# 1_Shutdown.net
KiCad netlist of a schematic drawn in Altium Designer
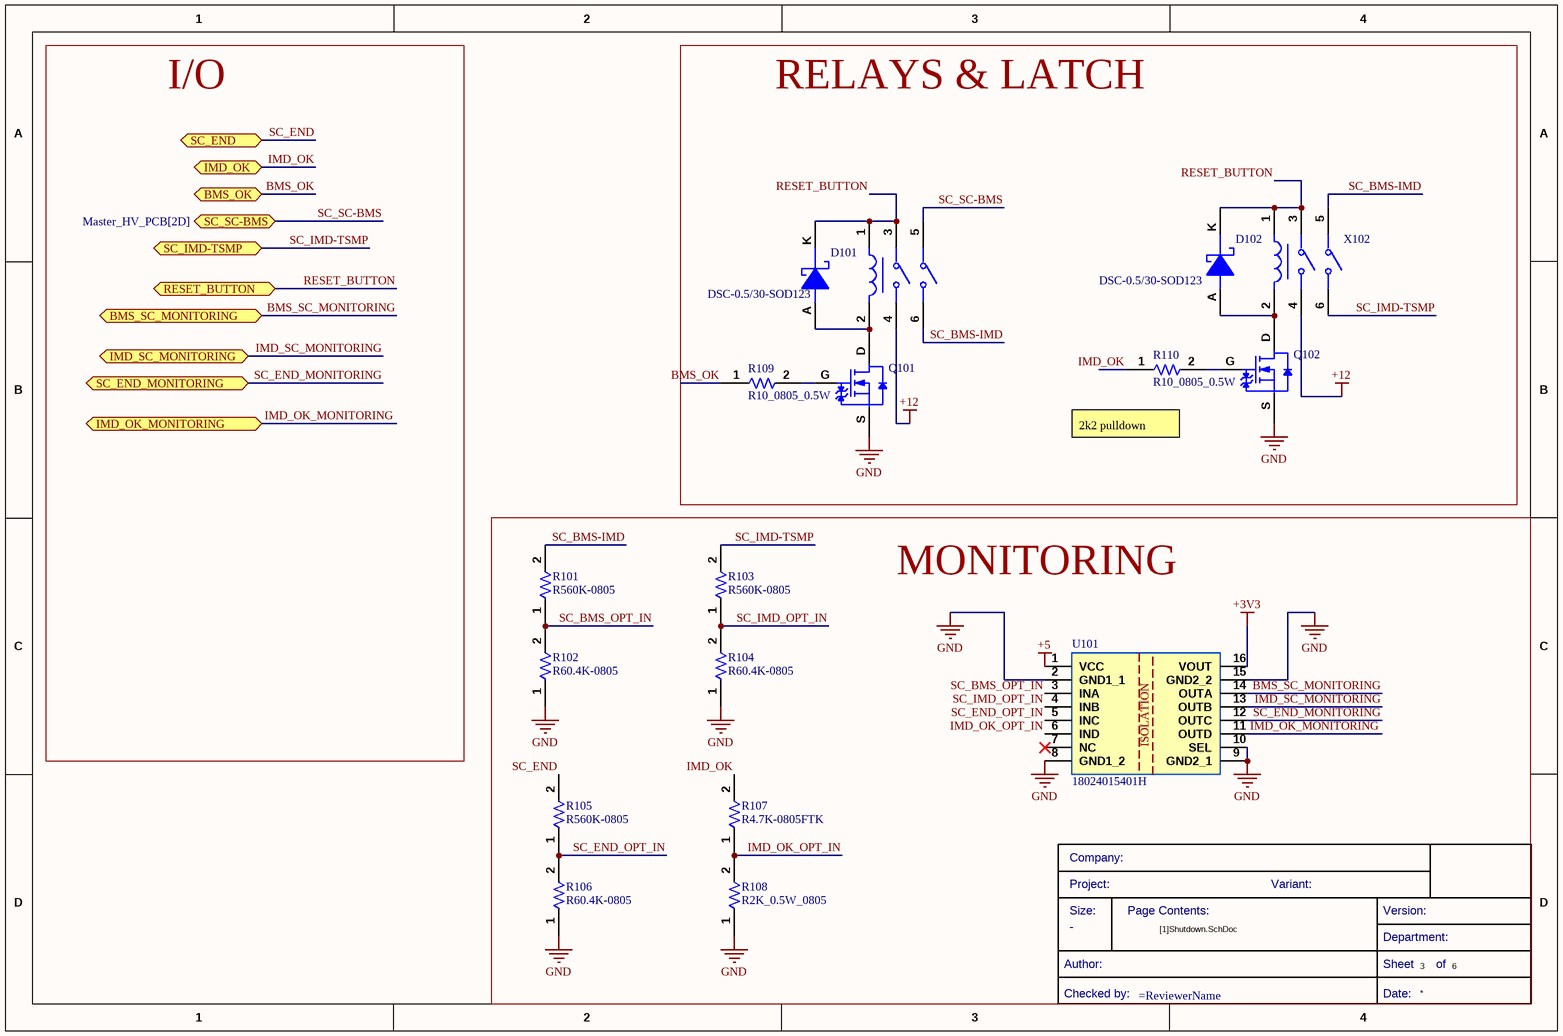
[diagram p0: [1]Shutdown.SchDoc]

(export (version "E")
  (design (tool "Eeschema 10.0.6"))
  (components
    (comp (ref "D101")
      (value "DSC-0.5/30-SOD123")
      (footprint "DSC-SOD123")
      (description "VR=30V IF=500mA 30pF P=410mW")
      (fields (field (name ".CREATOR") "GP"))
      (libsource (lib "EMEA- E-Tech Racing- I'Escola d'Enginyeria de Barcelona Est") (part "DSC-0.5/30-SOD123"))
    )
    (comp (ref "D102")
      (value "DSC-0.5/30-SOD123")
      (footprint "DSC-SOD123")
      (description "VR=30V IF=500mA 30pF P=410mW")
      (fields (field (name ".CREATOR") "GP"))
      (libsource (lib "EMEA- E-Tech Racing- I'Escola d'Enginyeria de Barcelona Est") (part "DSC-0.5/30-SOD123"))
    )
    (comp (ref "Q101")
      (value "SQ2318CES-T1_GE3")
      (footprint "SOT95P245X110-3N")
      (description "Mosfet, N-channel, 40V, 7A, SOT-23 Rohs Compliant: Yes")
      (libsource (lib "EMEA- E-Tech Racing- I'Escola d'Enginyeria de Barcelona Est") (part "TRT-NCH-3/35-CPH"))
    )
    (comp (ref "Q102")
      (value "SQ2318CES-T1_GE3")
      (footprint "SOT95P245X110-3N")
      (description "Mosfet, N-channel, 40V, 7A, SOT-23 Rohs Compliant: Yes")
      (libsource (lib "EMEA- E-Tech Racing- I'Escola d'Enginyeria de Barcelona Est") (part "TRT-NCH-3/35-CPH"))
    )
    (comp (ref "R101")
      (value "R560K-0805")
      (footprint "0805")
      (fields (field (name "POWER") "125mW") (field (name "TOLERANCE") "1%"))
      (libsource (lib "EMEA- E-Tech Racing- I'Escola d'Enginyeria de Barcelona Est") (part "R9.09K-1206FTK"))
    )
    (comp (ref "R102")
      (value "R60.4K-0805")
      (footprint "FP-CR0805-IPC_A")
      (fields (field (name "TOLERANCE") "1%") (field (name "POWER") "125mW"))
      (libsource (lib "EMEA- E-Tech Racing- I'Escola d'Enginyeria de Barcelona Est") (part "R9.09K-1206FTK"))
    )
    (comp (ref "R103")
      (value "R560K-0805")
      (footprint "0805")
      (fields (field (name "POWER") "125mW") (field (name "TOLERANCE") "1%"))
      (libsource (lib "EMEA- E-Tech Racing- I'Escola d'Enginyeria de Barcelona Est") (part "R9.09K-1206FTK"))
    )
    (comp (ref "R104")
      (value "R60.4K-0805")
      (footprint "FP-CR0805-IPC_A")
      (fields (field (name "TOLERANCE") "1%") (field (name "POWER") "125mW"))
      (libsource (lib "EMEA- E-Tech Racing- I'Escola d'Enginyeria de Barcelona Est") (part "R9.09K-1206FTK"))
    )
    (comp (ref "R105")
      (value "R560K-0805")
      (footprint "0805")
      (fields (field (name "POWER") "125mW") (field (name "TOLERANCE") "1%"))
      (libsource (lib "EMEA- E-Tech Racing- I'Escola d'Enginyeria de Barcelona Est") (part "R9.09K-1206FTK"))
    )
    (comp (ref "R106")
      (value "R60.4K-0805")
      (footprint "FP-CR0805-IPC_A")
      (fields (field (name "TOLERANCE") "1%") (field (name "POWER") "125mW"))
      (libsource (lib "EMEA- E-Tech Racing- I'Escola d'Enginyeria de Barcelona Est") (part "R9.09K-1206FTK"))
    )
    (comp (ref "R107")
      (value "R4.7K-0805FTK")
      (footprint "R0805FTK")
      (description "Res Thick Film 0805 4.7K Ohm 5% 1/8W ±200ppm/°C Molded SMD SMD Paper Tape on Plastic Reel")
      (fields (field (name "TOLERANCE") "5%") (field (name ".CREATOR") "DR"))
      (libsource (lib "EMEA- E-Tech Racing- I'Escola d'Enginyeria de Barcelona Est") (part "R9.09K-1206FTK"))
    )
    (comp (ref "R108")
      (value "R2K_0.5W_0805")
      (footprint "0805")
      (fields
        (field (name "POWER") "500mW")
        (field (name "TOLERANCE") "1%")
        (field (name "PART NUMBER") "CRCW08052K00FKEAHP")
      )
      (libsource (lib "EMEA- E-Tech Racing- I'Escola d'Enginyeria de Barcelona Est") (part "R9.09K-1206FTK"))
    )
    (comp (ref "R109")
      (value "R10_0805_0.5W")
      (footprint "0805")
      (fields (field (name "TOLERANCE") "1%") (field (name "POWER") "500mW"))
      (libsource (lib "EMEA- E-Tech Racing- I'Escola d'Enginyeria de Barcelona Est") (part "R9.09K-1206FTK"))
    )
    (comp (ref "R110")
      (value "R10_0805_0.5W")
      (footprint "0805")
      (fields (field (name "TOLERANCE") "1%") (field (name "POWER") "500mW"))
      (libsource (lib "EMEA- E-Tech Racing- I'Escola d'Enginyeria de Barcelona Est") (part "R9.09K-1206FTK"))
    )
    (comp (ref "U101")
      (value "18024015401H")
      (footprint "18024015401H")
      (description "Digital Isolator, 4CH, 125DEG C, WSOIC16 Rohs Compliant: Yes")
      (libsource (lib "EMEA- E-Tech Racing- I'Escola d'Enginyeria de Barcelona Est") (part "18024015401H"))
    )
    (comp (ref "X101")
      (value "RTE44012F")
      (footprint "RTE44012F-Footprint-1")
      (libsource (lib "EMEA- E-Tech Racing- I'Escola d'Enginyeria de Barcelona Est") (part "Relay_G81C"))
    )
    (comp (ref "X102")
      (value "RTE44012F")
      (footprint "RTE44012F-Footprint-1")
      (libsource (lib "EMEA- E-Tech Racing- I'Escola d'Enginyeria de Barcelona Est") (part "Relay_G81C"))
    )
  )
  (nets
    (net (code "1") (name "+3V3") (class "Default")
      (node (ref "U101") (pin "16") (pinfunction "VOUT_16") (pintype "passive"))
    )
    (net (code "2") (name "+5") (class "Default")
      (node (ref "U101") (pin "1") (pinfunction "VCC_1") (pintype "passive"))
    )
    (net (code "3") (name "+12") (class "Default")
      (node (ref "X101") (pin "4") (pinfunction "4_4") (pintype "passive"))
      (node (ref "X102") (pin "4") (pinfunction "4_4") (pintype "passive"))
    )
    (net (code "4") (name "/BMS_OK") (class "Default")
      (node (ref "R109") (pin "1") (pinfunction "1_1") (pintype "passive"))
    )
    (net (code "5") (name "/BMS_SC_MONITORING") (class "Default")
      (node (ref "U101") (pin "14") (pinfunction "OUTA_14") (pintype "passive"))
    )
    (net (code "6") (name "/IMD_OK") (class "Default")
      (node (ref "R107") (pin "2") (pinfunction "2_2") (pintype "passive"))
      (node (ref "R110") (pin "1") (pinfunction "1_1") (pintype "passive"))
    )
    (net (code "7") (name "/IMD_OK_MONITORING") (class "Default")
      (node (ref "U101") (pin "11") (pinfunction "OUTD_11") (pintype "passive"))
    )
    (net (code "8") (name "/IMD_OK_OPT_IN") (class "Default")
      (node (ref "R107") (pin "1") (pinfunction "1_1") (pintype "passive"))
      (node (ref "R108") (pin "2") (pinfunction "2_2") (pintype "passive"))
      (node (ref "U101") (pin "6") (pinfunction "IND_6") (pintype "passive"))
    )
    (net (code "9") (name "/IMD_SC_MONITORING") (class "Default")
      (node (ref "U101") (pin "13") (pinfunction "OUTB_13") (pintype "passive"))
    )
    (net (code "10") (name "/RESET_BUTTON") (class "Default")
      (node (ref "D101") (pin "K") (pinfunction "K_K") (pintype "passive"))
      (node (ref "D102") (pin "K") (pinfunction "K_K") (pintype "passive"))
      (node (ref "X101") (pin "1") (pinfunction "1_1") (pintype "passive"))
      (node (ref "X101") (pin "3") (pinfunction "3_3") (pintype "passive"))
      (node (ref "X102") (pin "1") (pinfunction "1_1") (pintype "passive"))
      (node (ref "X102") (pin "3") (pinfunction "3_3") (pintype "passive"))
    )
    (net (code "11") (name "/SC_BMS-IMD") (class "Default")
      (node (ref "R101") (pin "2") (pinfunction "2_2") (pintype "passive"))
      (node (ref "X101") (pin "6") (pinfunction "6_6") (pintype "passive"))
      (node (ref "X102") (pin "5") (pinfunction "5_5") (pintype "passive"))
    )
    (net (code "12") (name "/SC_BMS_OPT_IN") (class "Default")
      (node (ref "R101") (pin "1") (pinfunction "1_1") (pintype "passive"))
      (node (ref "R102") (pin "2") (pinfunction "2_2") (pintype "passive"))
      (node (ref "U101") (pin "3") (pinfunction "INA_3") (pintype "passive"))
    )
    (net (code "13") (name "/SC_END") (class "Default")
      (node (ref "R105") (pin "2") (pinfunction "2_2") (pintype "passive"))
    )
    (net (code "14") (name "/SC_END_MONITORING") (class "Default")
      (node (ref "U101") (pin "12") (pinfunction "OUTC_12") (pintype "passive"))
    )
    (net (code "15") (name "/SC_END_OPT_IN") (class "Default")
      (node (ref "R105") (pin "1") (pinfunction "1_1") (pintype "passive"))
      (node (ref "R106") (pin "2") (pinfunction "2_2") (pintype "passive"))
      (node (ref "U101") (pin "5") (pinfunction "INC_5") (pintype "passive"))
    )
    (net (code "16") (name "/SC_IMD-TSMP") (class "Default")
      (node (ref "R103") (pin "2") (pinfunction "2_2") (pintype "passive"))
      (node (ref "X102") (pin "6") (pinfunction "6_6") (pintype "passive"))
    )
    (net (code "17") (name "/SC_IMD_OPT_IN") (class "Default")
      (node (ref "R103") (pin "1") (pinfunction "1_1") (pintype "passive"))
      (node (ref "R104") (pin "2") (pinfunction "2_2") (pintype "passive"))
      (node (ref "U101") (pin "4") (pinfunction "INB_4") (pintype "passive"))
    )
    (net (code "18") (name "/SC_SC-BMS") (class "Default")
      (node (ref "X101") (pin "5") (pinfunction "5_5") (pintype "passive"))
    )
    (net (code "19") (name "GND") (class "Default")
      (node (ref "Q101") (pin "S") (pinfunction "S_S") (pintype "passive"))
      (node (ref "Q102") (pin "S") (pinfunction "S_S") (pintype "passive"))
      (node (ref "R102") (pin "1") (pinfunction "1_1") (pintype "passive"))
      (node (ref "R104") (pin "1") (pinfunction "1_1") (pintype "passive"))
      (node (ref "R106") (pin "1") (pinfunction "1_1") (pintype "passive"))
      (node (ref "R108") (pin "1") (pinfunction "1_1") (pintype "passive"))
      (node (ref "U101") (pin "10") (pinfunction "SEL_10") (pintype "passive"))
      (node (ref "U101") (pin "15") (pinfunction "GND2_2_15") (pintype "passive"))
      (node (ref "U101") (pin "2") (pinfunction "GND1_1_2") (pintype "passive"))
      (node (ref "U101") (pin "8") (pinfunction "GND1_2_8") (pintype "passive"))
      (node (ref "U101") (pin "9") (pinfunction "GND2_1_9") (pintype "passive"))
    )
    (net (code "20") (name "Net-(D101-PadA)") (class "Default")
      (node (ref "D101") (pin "A") (pinfunction "A_A") (pintype "passive"))
      (node (ref "Q101") (pin "D") (pinfunction "D_D") (pintype "passive"))
      (node (ref "X101") (pin "2") (pinfunction "2_2") (pintype "passive"))
    )
    (net (code "21") (name "Net-(D102-PadA)") (class "Default")
      (node (ref "D102") (pin "A") (pinfunction "A_A") (pintype "passive"))
      (node (ref "Q102") (pin "D") (pinfunction "D_D") (pintype "passive"))
      (node (ref "X102") (pin "2") (pinfunction "2_2") (pintype "passive"))
    )
    (net (code "22") (name "Net-(Q101-PadG)") (class "Default")
      (node (ref "Q101") (pin "G") (pinfunction "G_G") (pintype "passive"))
      (node (ref "R109") (pin "2") (pinfunction "2_2") (pintype "passive"))
    )
    (net (code "23") (name "Net-(Q102-PadG)") (class "Default")
      (node (ref "Q102") (pin "G") (pinfunction "G_G") (pintype "passive"))
      (node (ref "R110") (pin "2") (pinfunction "2_2") (pintype "passive"))
    )
    (net (code "24") (name "unconnected-(U101-NC-Pad7)") (class "Default")
      (node (ref "U101") (pin "7") (pinfunction "NC_7") (pintype "passive+no_connect"))
    )
  )
)
